# led-matrix-headers-separate.net
KiCad netlist of a schematic drawn in EAGLE
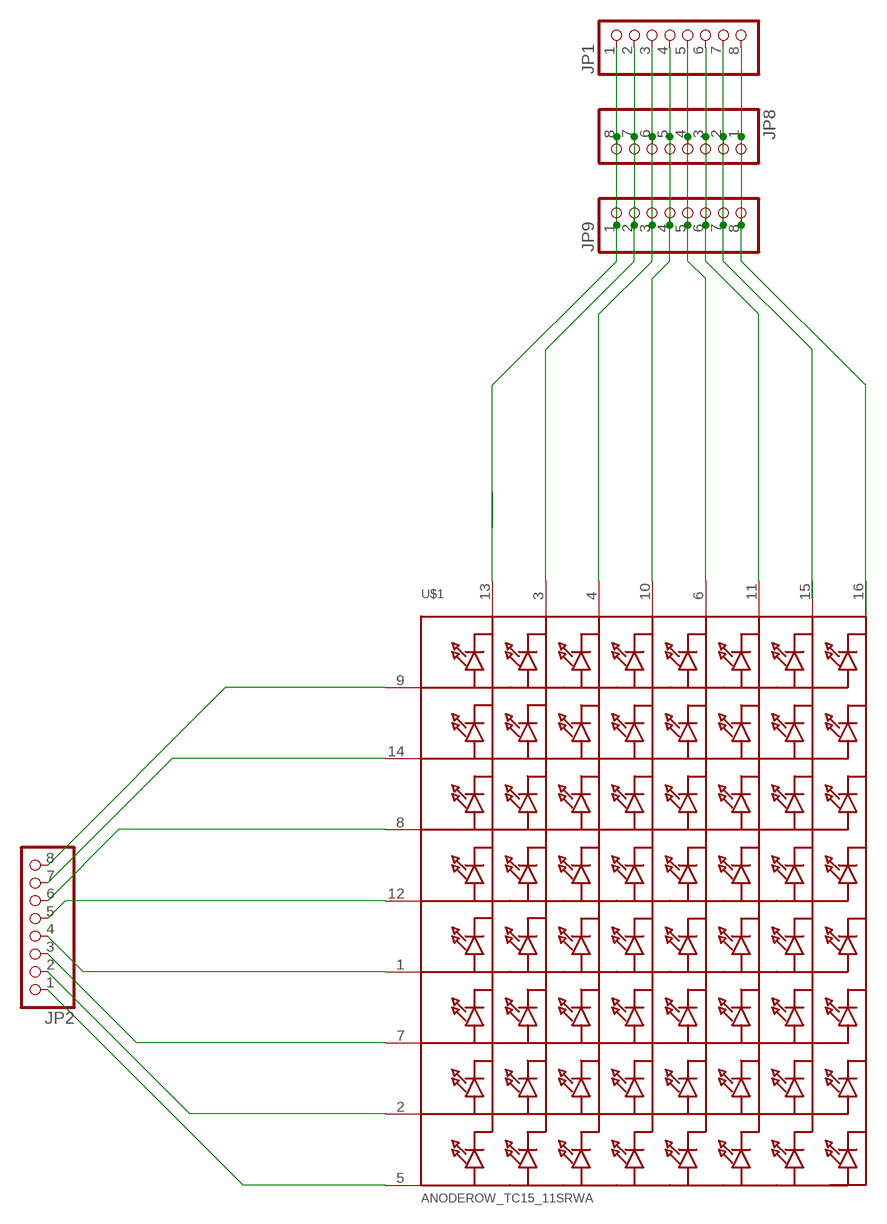
[diagram p0: schematic, sheet 1]

(export (version "E")
  (design (tool "Eeschema 10.0.6"))
  (components
    (comp (ref "JP1")
      (value "PINHD-1X8/OCT")
      (footprint "eagle-import:1X08_OCT")
      (libsource (lib "eagle-import") (part "PINHD-1X8/OCT"))
    )
    (comp (ref "JP2")
      (value "PINHD-1X8/OCT")
      (footprint "eagle-import:1X08_OCT")
      (libsource (lib "eagle-import") (part "PINHD-1X8/OCT"))
    )
    (comp (ref "JP8")
      (value "PINHD-1X8/OCT")
      (footprint "eagle-import:1X08_OCT")
      (libsource (lib "eagle-import") (part "PINHD-1X8/OCT"))
    )
    (comp (ref "JP9")
      (value "PINHD-1X8/OCT")
      (footprint "eagle-import:1X08_OCT")
      (libsource (lib "eagle-import") (part "PINHD-1X8/OCT"))
    )
    (comp (ref "U$1")
      (value "ANODEROW_TC15_11SRWA")
      (footprint "eagle-import:SEGMENT_TC15-11SRWA")
      (libsource (lib "eagle-import") (part "ANODEROW_TC15_11SRWA"))
    )
  )
  (nets
    (net (code "1") (name "Net-(U$1-A1)") (class "Default")
      (node (ref "JP2") (pin "8") (pinfunction "8_8") (pintype "passive"))
      (node (ref "U$1") (pin "9") (pinfunction "A1_9") (pintype "bidirectional"))
    )
    (net (code "2") (name "Net-(U$1-A2)") (class "Default")
      (node (ref "JP2") (pin "7") (pinfunction "7_7") (pintype "passive"))
      (node (ref "U$1") (pin "14") (pinfunction "A2_14") (pintype "bidirectional"))
    )
    (net (code "3") (name "Net-(U$1-A3)") (class "Default")
      (node (ref "JP2") (pin "6") (pinfunction "6_6") (pintype "passive"))
      (node (ref "U$1") (pin "8") (pinfunction "A3_8") (pintype "bidirectional"))
    )
    (net (code "4") (name "Net-(U$1-A4)") (class "Default")
      (node (ref "JP2") (pin "5") (pinfunction "5_5") (pintype "passive"))
      (node (ref "U$1") (pin "12") (pinfunction "A4_12") (pintype "bidirectional"))
    )
    (net (code "5") (name "Net-(U$1-A5)") (class "Default")
      (node (ref "JP2") (pin "4") (pinfunction "4_4") (pintype "passive"))
      (node (ref "U$1") (pin "1") (pinfunction "A5_1") (pintype "bidirectional"))
    )
    (net (code "6") (name "Net-(U$1-A6)") (class "Default")
      (node (ref "JP2") (pin "3") (pinfunction "3_3") (pintype "passive"))
      (node (ref "U$1") (pin "7") (pinfunction "A6_7") (pintype "bidirectional"))
    )
    (net (code "7") (name "Net-(U$1-A7)") (class "Default")
      (node (ref "JP2") (pin "2") (pinfunction "2_2") (pintype "passive"))
      (node (ref "U$1") (pin "2") (pinfunction "A7_2") (pintype "bidirectional"))
    )
    (net (code "8") (name "Net-(U$1-A8)") (class "Default")
      (node (ref "JP2") (pin "1") (pinfunction "1_1") (pintype "passive"))
      (node (ref "U$1") (pin "5") (pinfunction "A8_5") (pintype "bidirectional"))
    )
    (net (code "9") (name "Net-(U$1-K1)") (class "Default")
      (node (ref "JP1") (pin "1") (pinfunction "1_1") (pintype "passive"))
      (node (ref "JP8") (pin "8") (pinfunction "8_8") (pintype "passive"))
      (node (ref "JP9") (pin "1") (pinfunction "1_1") (pintype "passive"))
      (node (ref "U$1") (pin "13") (pinfunction "K1_13") (pintype "bidirectional"))
    )
    (net (code "10") (name "Net-(U$1-K2)") (class "Default")
      (node (ref "JP1") (pin "2") (pinfunction "2_2") (pintype "passive"))
      (node (ref "JP8") (pin "7") (pinfunction "7_7") (pintype "passive"))
      (node (ref "JP9") (pin "2") (pinfunction "2_2") (pintype "passive"))
      (node (ref "U$1") (pin "3") (pinfunction "K2_3") (pintype "bidirectional"))
    )
    (net (code "11") (name "Net-(U$1-K3)") (class "Default")
      (node (ref "JP1") (pin "3") (pinfunction "3_3") (pintype "passive"))
      (node (ref "JP8") (pin "6") (pinfunction "6_6") (pintype "passive"))
      (node (ref "JP9") (pin "3") (pinfunction "3_3") (pintype "passive"))
      (node (ref "U$1") (pin "4") (pinfunction "K3_4") (pintype "bidirectional"))
    )
    (net (code "12") (name "Net-(U$1-K4)") (class "Default")
      (node (ref "JP1") (pin "4") (pinfunction "4_4") (pintype "passive"))
      (node (ref "JP8") (pin "5") (pinfunction "5_5") (pintype "passive"))
      (node (ref "JP9") (pin "4") (pinfunction "4_4") (pintype "passive"))
      (node (ref "U$1") (pin "10") (pinfunction "K4_10") (pintype "bidirectional"))
    )
    (net (code "13") (name "Net-(U$1-K5)") (class "Default")
      (node (ref "JP1") (pin "5") (pinfunction "5_5") (pintype "passive"))
      (node (ref "JP8") (pin "4") (pinfunction "4_4") (pintype "passive"))
      (node (ref "JP9") (pin "5") (pinfunction "5_5") (pintype "passive"))
      (node (ref "U$1") (pin "6") (pinfunction "K5_6") (pintype "bidirectional"))
    )
    (net (code "14") (name "Net-(U$1-K6)") (class "Default")
      (node (ref "JP1") (pin "6") (pinfunction "6_6") (pintype "passive"))
      (node (ref "JP8") (pin "3") (pinfunction "3_3") (pintype "passive"))
      (node (ref "JP9") (pin "6") (pinfunction "6_6") (pintype "passive"))
      (node (ref "U$1") (pin "11") (pinfunction "K6_11") (pintype "bidirectional"))
    )
    (net (code "15") (name "Net-(U$1-K7)") (class "Default")
      (node (ref "JP1") (pin "7") (pinfunction "7_7") (pintype "passive"))
      (node (ref "JP8") (pin "2") (pinfunction "2_2") (pintype "passive"))
      (node (ref "JP9") (pin "7") (pinfunction "7_7") (pintype "passive"))
      (node (ref "U$1") (pin "15") (pinfunction "K7_15") (pintype "bidirectional"))
    )
    (net (code "16") (name "Net-(U$1-K8)") (class "Default")
      (node (ref "JP1") (pin "8") (pinfunction "8_8") (pintype "passive"))
      (node (ref "JP8") (pin "1") (pinfunction "1_1") (pintype "passive"))
      (node (ref "JP9") (pin "8") (pinfunction "8_8") (pintype "passive"))
      (node (ref "U$1") (pin "16") (pinfunction "K8_16") (pintype "bidirectional"))
    )
  )
)
